# LAMEBOY.net
KiCad netlist of a schematic drawn in EAGLE
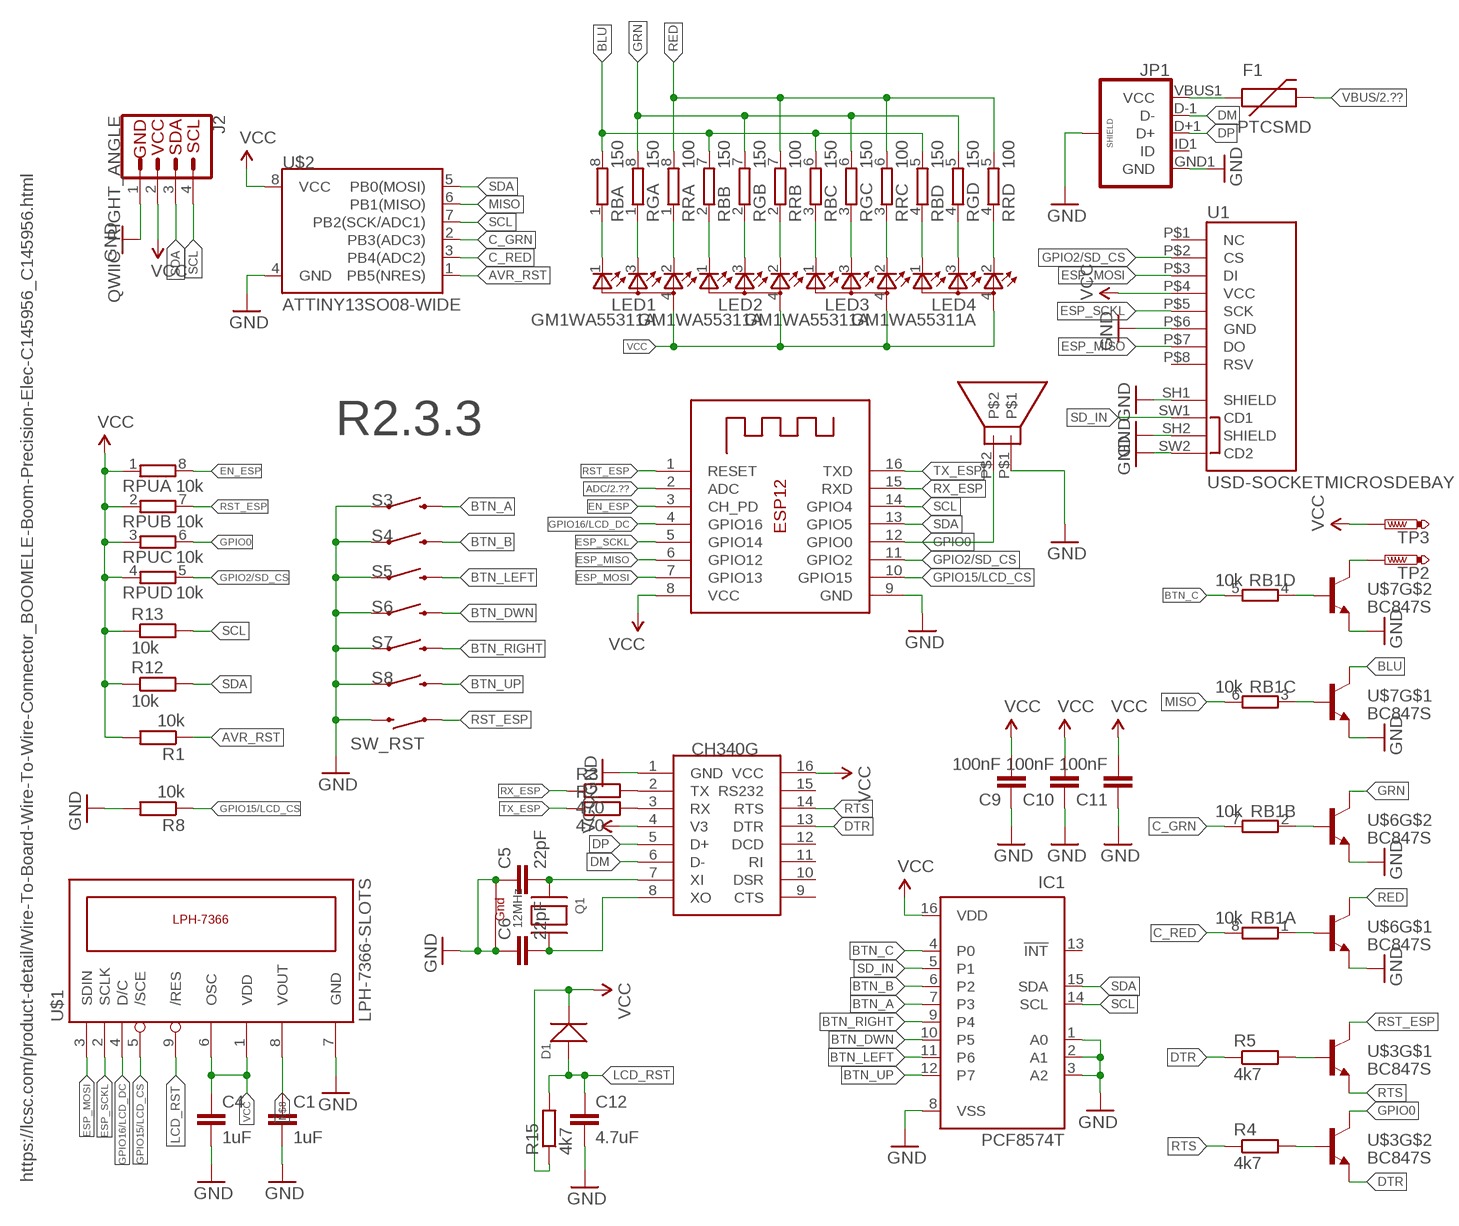
[diagram p0: schematic, sheet 1]
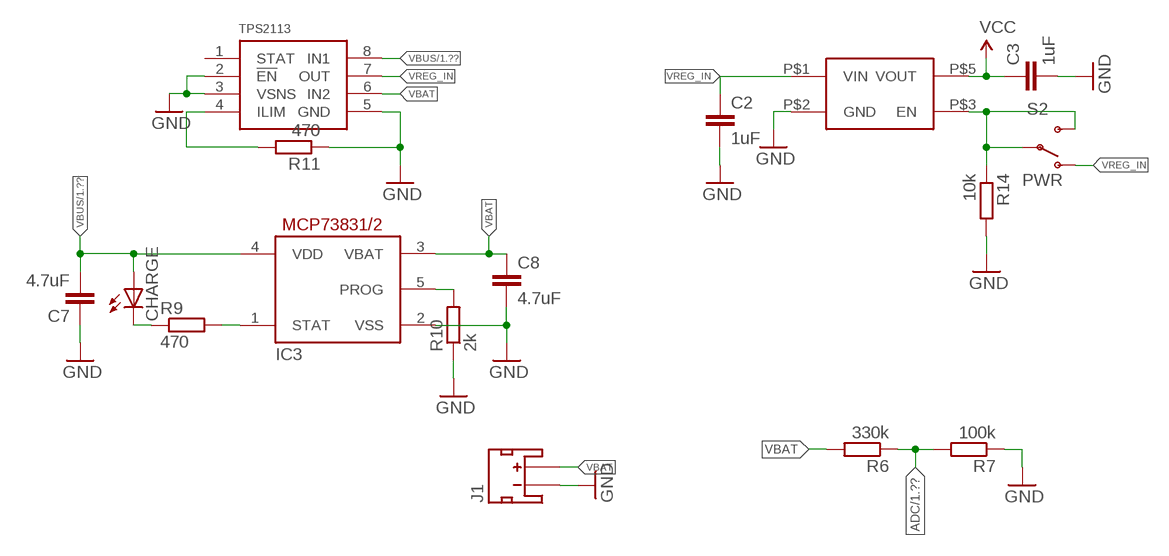
[diagram p1: schematic, sheet 2]

(export (version "E")
  (design (tool "Eeschema 10.0.6"))
  (components
    (comp (ref "C2")
      (value "1uF")
      (footprint "eagle-import:C0805")
      (libsource (lib "eagle-import") (part "C-EUC0805"))
    )
    (comp (ref "C3")
      (value "1uF")
      (footprint "eagle-import:C0805")
      (libsource (lib "eagle-import") (part "C-EUC0805"))
    )
    (comp (ref "C7")
      (value "4.7uF")
      (footprint "eagle-import:C0805")
      (libsource (lib "eagle-import") (part "C-EUC0805"))
    )
    (comp (ref "C8")
      (value "4.7uF")
      (footprint "eagle-import:C0805")
      (libsource (lib "eagle-import") (part "C-EUC0805"))
    )
    (comp (ref "CHARGE")
      (value "LEDCHARLIE")
      (footprint "eagle-import:CHIPLED_0603_CHARLIE")
      (libsource (lib "eagle-import") (part "LEDCHARLIE"))
    )
    (comp (ref "IC3")
      (value "MCP73831")
      (footprint "eagle-import:SOT23-5L")
      (libsource (lib "eagle-import") (part "MCP73831/OT"))
    )
    (comp (ref "J1")
      (value "JST_2MM_MALE")
      (footprint "eagle-import:JST-2-SMD")
      (libsource (lib "eagle-import") (part "JST_2MM_MALE"))
    )
    (comp (ref "R6")
      (value "330k")
      (footprint "eagle-import:R0603")
      (libsource (lib "eagle-import") (part "R-EU_R0603"))
    )
    (comp (ref "R7")
      (value "100k")
      (footprint "eagle-import:R0603")
      (libsource (lib "eagle-import") (part "R-EU_R0603"))
    )
    (comp (ref "R9")
      (value "470")
      (footprint "eagle-import:R0603")
      (libsource (lib "eagle-import") (part "R-EU_R0603"))
    )
    (comp (ref "R10")
      (value "2k")
      (footprint "eagle-import:R0603")
      (libsource (lib "eagle-import") (part "R-EU_R0603"))
    )
    (comp (ref "R11")
      (value "470")
      (footprint "eagle-import:R0603")
      (libsource (lib "eagle-import") (part "R-EU_R0603"))
    )
    (comp (ref "R14")
      (value "10k")
      (footprint "eagle-import:R0603")
      (libsource (lib "eagle-import") (part "R-EU_R0603"))
    )
    (comp (ref "S2")
      (value "PWR")
      (footprint "eagle-import:SWITCH-SPST-SMD-A")
      (libsource (lib "eagle-import") (part "SWITCH-SPDT-SMD-A"))
    )
    (comp (ref "U$4")
      (value "TPS2113-PW")
      (footprint "eagle-import:TEXAS-PW")
      (libsource (lib "eagle-import") (part "TPS2113-PW"))
    )
    (comp (ref "U$9")
      (value "AP2112KAP2112K")
      (footprint "eagle-import:AP2112")
      (libsource (lib "eagle-import") (part "AP2112KAP2112K"))
    )
    (comp (ref "C1")
      (value "1uF")
      (footprint "eagle-import:C0805")
      (libsource (lib "eagle-import") (part "C-EUC0805"))
    )
    (comp (ref "C4")
      (value "1uF")
      (footprint "eagle-import:C0805")
      (libsource (lib "eagle-import") (part "C-EUC0805"))
    )
    (comp (ref "C5")
      (value "22pF")
      (footprint "eagle-import:C0805")
      (libsource (lib "eagle-import") (part "C-EUC0805"))
    )
    (comp (ref "C6")
      (value "22pF")
      (footprint "eagle-import:C0805")
      (libsource (lib "eagle-import") (part "C-EUC0805"))
    )
    (comp (ref "C9")
      (value "100nF")
      (footprint "eagle-import:C0805")
      (libsource (lib "eagle-import") (part "C-EUC0805"))
    )
    (comp (ref "C10")
      (value "100nF")
      (footprint "eagle-import:C0805")
      (libsource (lib "eagle-import") (part "C-EUC0805"))
    )
    (comp (ref "C11")
      (value "100nF")
      (footprint "eagle-import:C0805")
      (libsource (lib "eagle-import") (part "C-EUC0805"))
    )
    (comp (ref "C12")
      (value "4.7uF")
      (footprint "eagle-import:C0805")
      (libsource (lib "eagle-import") (part "C-EUC0805"))
    )
    (comp (ref "CH340G")
      (value "CH340GCH340G")
      (footprint "eagle-import:SOIC16")
      (libsource (lib "eagle-import") (part "CH340GCH340G"))
    )
    (comp (ref "D1")
      (value "DIODE'1N4148-SMD'")
      (footprint "eagle-import:LL-34")
      (libsource (lib "eagle-import") (part "DIODE'1N4148-SMD'"))
    )
    (comp (ref "F1")
      (value "PTCSMD")
      (footprint "eagle-import:PTC-1206")
      (libsource (lib "eagle-import") (part "PTCSMD"))
    )
    (comp (ref "IC1")
      (value "PCF8574T")
      (footprint "eagle-import:SO16W")
      (fields (field (name "MPN") "PCF8574T/3,512"))
      (libsource (lib "eagle-import") (part "PCF8574T"))
    )
    (comp (ref "J2")
      (value "QWIIC_RIGHT_ANGLE")
      (footprint "eagle-import:JST04_1MM_RA")
      (libsource (lib "eagle-import") (part "QWIIC_CONNECTORJS-1MM"))
    )
    (comp (ref "JP1")
      (value "USB_MICROB_PLUG-IDK")
      (footprint "eagle-import:USB-AB-MICRO-SMD_SLOT")
      (libsource (lib "eagle-import") (part "USB_MICROB_PLUG-IDK"))
    )
    (comp (ref "LED1")
      (value "GM1WA55311A")
      (footprint "eagle-import:GM1WA55311A")
      (libsource (lib "eagle-import") (part "GM1WA55311A"))
    )
    (comp (ref "LED2")
      (value "GM1WA55311A")
      (footprint "eagle-import:GM1WA55311A")
      (libsource (lib "eagle-import") (part "GM1WA55311A"))
    )
    (comp (ref "LED3")
      (value "GM1WA55311A")
      (footprint "eagle-import:GM1WA55311A")
      (libsource (lib "eagle-import") (part "GM1WA55311A"))
    )
    (comp (ref "LED4")
      (value "GM1WA55311A")
      (footprint "eagle-import:GM1WA55311A")
      (libsource (lib "eagle-import") (part "GM1WA55311A"))
    )
    (comp (ref "Q1")
      (value "12MHz")
      (footprint "eagle-import:NX3225_BIGGER")
      (libsource (lib "eagle-import") (part "XTAL-4BIGGER"))
    )
    (comp (ref "R1")
      (value "10k")
      (footprint "eagle-import:R0603")
      (libsource (lib "eagle-import") (part "R-EU_R0603"))
    )
    (comp (ref "R2")
      (value "470")
      (footprint "eagle-import:R0603")
      (libsource (lib "eagle-import") (part "R-EU_R0603"))
    )
    (comp (ref "R3")
      (value "470")
      (footprint "eagle-import:R0603")
      (libsource (lib "eagle-import") (part "R-EU_R0603"))
    )
    (comp (ref "R4")
      (value "4k7")
      (footprint "eagle-import:R0603")
      (libsource (lib "eagle-import") (part "R-EU_R0603"))
    )
    (comp (ref "R5")
      (value "4k7")
      (footprint "eagle-import:R0603")
      (libsource (lib "eagle-import") (part "R-EU_R0603"))
    )
    (comp (ref "R8")
      (value "10k")
      (footprint "eagle-import:R0603")
      (libsource (lib "eagle-import") (part "R-EU_R0603"))
    )
    (comp (ref "R12")
      (value "10k")
      (footprint "eagle-import:R0603")
      (libsource (lib "eagle-import") (part "R-EU_R0603"))
    )
    (comp (ref "R13")
      (value "10k")
      (footprint "eagle-import:R0603")
      (libsource (lib "eagle-import") (part "R-EU_R0603"))
    )
    (comp (ref "R15")
      (value "4k7")
      (footprint "eagle-import:R0603")
      (libsource (lib "eagle-import") (part "R-EU_R0603"))
    )
    (comp (ref "RB")
      (value "150")
      (footprint "eagle-import:0603-ARC")
      (libsource (lib "eagle-import") (part "4R-N0603-ARC"))
    )
    (comp (ref "RB1")
      (value "10k")
      (footprint "eagle-import:0603-ARC")
      (libsource (lib "eagle-import") (part "4R-N0603-ARC"))
    )
    (comp (ref "RG")
      (value "150")
      (footprint "eagle-import:0603-ARC")
      (libsource (lib "eagle-import") (part "4R-N0603-ARC"))
    )
    (comp (ref "RPU")
      (value "10k")
      (footprint "eagle-import:0603-ARC")
      (libsource (lib "eagle-import") (part "4R-N0603-ARC"))
    )
    (comp (ref "RR")
      (value "100")
      (footprint "eagle-import:0603-ARC")
      (libsource (lib "eagle-import") (part "4R-N0603-ARC"))
    )
    (comp (ref "S3")
      (value "SWITCH-MOMENTARY-2SMD-4")
      (footprint "eagle-import:TACTILE_SWITCH_TALL")
      (libsource (lib "eagle-import") (part "SWITCH-MOMENTARY-2SMD-4"))
    )
    (comp (ref "S4")
      (value "SWITCH-MOMENTARY-2SMD-4")
      (footprint "eagle-import:TACTILE_SWITCH_TALL")
      (libsource (lib "eagle-import") (part "SWITCH-MOMENTARY-2SMD-4"))
    )
    (comp (ref "S5")
      (value "SWITCH-MOMENTARY-2SMD-4")
      (footprint "eagle-import:TACTILE_SWITCH_TALL")
      (libsource (lib "eagle-import") (part "SWITCH-MOMENTARY-2SMD-4"))
    )
    (comp (ref "S6")
      (value "SWITCH-MOMENTARY-2SMD-4")
      (footprint "eagle-import:TACTILE_SWITCH_TALL")
      (libsource (lib "eagle-import") (part "SWITCH-MOMENTARY-2SMD-4"))
    )
    (comp (ref "S7")
      (value "SWITCH-MOMENTARY-2SMD-4")
      (footprint "eagle-import:TACTILE_SWITCH_TALL")
      (libsource (lib "eagle-import") (part "SWITCH-MOMENTARY-2SMD-4"))
    )
    (comp (ref "S8")
      (value "SWITCH-MOMENTARY-2SMD-4")
      (footprint "eagle-import:TACTILE_SWITCH_TALL")
      (libsource (lib "eagle-import") (part "SWITCH-MOMENTARY-2SMD-4"))
    )
    (comp (ref "SW_RST")
      (value "SWITCH-MOMENTARY-2-SMD-1101NE")
      (footprint "eagle-import:TACTILE-SWITCH-1101NE")
      (libsource (lib "eagle-import") (part "SWITCH-MOMENTARY-2-SMD-1101NE"))
    )
    (comp (ref "TP2")
      (value "PTR1B1,27")
      (footprint "eagle-import:B1,27")
      (libsource (lib "eagle-import") (part "PTR1B1,27"))
    )
    (comp (ref "TP3")
      (value "PTR1B1,27")
      (footprint "eagle-import:B1,27")
      (libsource (lib "eagle-import") (part "PTR1B1,27"))
    )
    (comp (ref "U$1")
      (value "LPH-7366-SLOTS")
      (footprint "eagle-import:LPH-7366-SLOTS")
      (libsource (lib "eagle-import") (part "LPH-7366-SLOTS"))
    )
    (comp (ref "U$2")
      (value "ATTINY13SO08-WIDE")
      (footprint "eagle-import:SO08-EIAJ")
      (libsource (lib "eagle-import") (part "ATTINY13SO08-WIDE"))
    )
    (comp (ref "U$3")
      (value "BC847S")
      (footprint "eagle-import:SOT363")
      (libsource (lib "eagle-import") (part "MMDT3904"))
    )
    (comp (ref "U$5")
      (value "SPEAKERKMTG-1102")
      (footprint "eagle-import:KMTG-1102")
      (libsource (lib "eagle-import") (part "SPEAKERKMTG-1102"))
    )
    (comp (ref "U$6")
      (value "BC847S")
      (footprint "eagle-import:SOT363")
      (libsource (lib "eagle-import") (part "MMDT3904"))
    )
    (comp (ref "U$7")
      (value "BC847S")
      (footprint "eagle-import:SOT363")
      (libsource (lib "eagle-import") (part "MMDT3904"))
    )
    (comp (ref "U1")
      (value "USD-SOCKETMICROSDEBAY")
      (footprint "eagle-import:MICRO-SD-SOCKET-EBAY")
      (libsource (lib "eagle-import") (part "USD-SOCKETMICROSDEBAY"))
    )
    (comp (ref "X1")
      (value "ESP-12")
      (footprint "eagle-import:ESP-12")
      (libsource (lib "eagle-import") (part "ESP-12"))
    )
  )
  (nets
    (net (code "1") (name "ADC") (class "Default")
      (node (ref "R6") (pin "1") (pinfunction "1_1") (pintype "passive"))
      (node (ref "R7") (pin "2") (pinfunction "2_2") (pintype "passive"))
      (node (ref "X1") (pin "2") (pinfunction "ADC_2") (pintype "passive"))
    )
    (net (code "2") (name "AVR_RST") (class "Default")
      (node (ref "R1") (pin "1") (pinfunction "1_1") (pintype "passive"))
      (node (ref "U$2") (pin "1") (pinfunction "PB5(NRES)_1") (pintype "bidirectional"))
    )
    (net (code "3") (name "BLU") (class "Default")
      (node (ref "RB") (pin "5") (pinfunction "2_5") (pintype "passive"))
      (node (ref "RB") (pin "6") (pinfunction "2_6") (pintype "passive"))
      (node (ref "RB") (pin "7") (pinfunction "2_7") (pintype "passive"))
      (node (ref "RB") (pin "8") (pinfunction "2_8") (pintype "passive"))
      (node (ref "U$7") (pin "3") (pinfunction "C_3") (pintype "passive"))
    )
    (net (code "4") (name "BTN_A") (class "Default")
      (node (ref "IC1") (pin "7") (pinfunction "P3_7") (pintype "bidirectional"))
      (node (ref "S3") (pin "B2") (pinfunction "2_B2") (pintype "passive"))
    )
    (net (code "5") (name "BTN_B") (class "Default")
      (node (ref "IC1") (pin "6") (pinfunction "P2_6") (pintype "bidirectional"))
      (node (ref "S4") (pin "B2") (pinfunction "2_B2") (pintype "passive"))
    )
    (net (code "6") (name "BTN_C") (class "Default")
      (node (ref "IC1") (pin "4") (pinfunction "P0_4") (pintype "bidirectional"))
      (node (ref "RB1") (pin "5") (pinfunction "2_5") (pintype "passive"))
    )
    (net (code "7") (name "BTN_DWN") (class "Default")
      (node (ref "IC1") (pin "10") (pinfunction "P5_10") (pintype "bidirectional"))
      (node (ref "S6") (pin "B2") (pinfunction "2_B2") (pintype "passive"))
    )
    (net (code "8") (name "BTN_LEFT") (class "Default")
      (node (ref "IC1") (pin "11") (pinfunction "P6_11") (pintype "bidirectional"))
      (node (ref "S5") (pin "B2") (pinfunction "2_B2") (pintype "passive"))
    )
    (net (code "9") (name "BTN_RIGHT") (class "Default")
      (node (ref "IC1") (pin "9") (pinfunction "P4_9") (pintype "bidirectional"))
      (node (ref "S7") (pin "B2") (pinfunction "2_B2") (pintype "passive"))
    )
    (net (code "10") (name "BTN_UP") (class "Default")
      (node (ref "IC1") (pin "12") (pinfunction "P7_12") (pintype "bidirectional"))
      (node (ref "S8") (pin "B2") (pinfunction "2_B2") (pintype "passive"))
    )
    (net (code "11") (name "C_GRN") (class "Default")
      (node (ref "RB1") (pin "7") (pinfunction "2_7") (pintype "passive"))
      (node (ref "U$2") (pin "2") (pinfunction "PB3(ADC3)_2") (pintype "bidirectional"))
    )
    (net (code "12") (name "C_RED") (class "Default")
      (node (ref "RB1") (pin "8") (pinfunction "2_8") (pintype "passive"))
      (node (ref "U$2") (pin "3") (pinfunction "PB4(ADC2)_3") (pintype "bidirectional"))
    )
    (net (code "13") (name "DM") (class "Default")
      (node (ref "CH340G") (pin "6") (pinfunction "D-_6") (pintype "bidirectional"))
      (node (ref "JP1") (pin "D-1") (pinfunction "D-_D-1") (pintype "bidirectional"))
    )
    (net (code "14") (name "DP") (class "Default")
      (node (ref "CH340G") (pin "5") (pinfunction "D+_5") (pintype "bidirectional"))
      (node (ref "JP1") (pin "D+1") (pinfunction "D+_D+1") (pintype "bidirectional"))
    )
    (net (code "15") (name "DTR") (class "Default")
      (node (ref "CH340G") (pin "13") (pinfunction "DTR_13") (pintype "bidirectional"))
      (node (ref "R5") (pin "1") (pinfunction "1_1") (pintype "passive"))
      (node (ref "U$3") (pin "1") (pinfunction "E_1") (pintype "passive"))
    )
    (net (code "16") (name "EN_ESP") (class "Default")
      (node (ref "RPU") (pin "8") (pinfunction "2_8") (pintype "passive"))
      (node (ref "X1") (pin "3") (pinfunction "CH_PD_3") (pintype "input"))
    )
    (net (code "17") (name "ESP_MISO") (class "Default")
      (node (ref "U1") (pin "P$7") (pinfunction "DO_P$7") (pintype "bidirectional"))
      (node (ref "X1") (pin "6") (pinfunction "GPIO12_6") (pintype "bidirectional"))
    )
    (net (code "18") (name "ESP_MOSI") (class "Default")
      (node (ref "U$1") (pin "3") (pinfunction "SDIN_3") (pintype "input"))
      (node (ref "U1") (pin "P$3") (pinfunction "DI_P$3") (pintype "bidirectional"))
      (node (ref "X1") (pin "7") (pinfunction "GPIO13_7") (pintype "bidirectional"))
    )
    (net (code "19") (name "ESP_SCKL") (class "Default")
      (node (ref "U$1") (pin "2") (pinfunction "SCLK_2") (pintype "input"))
      (node (ref "U1") (pin "P$5") (pinfunction "SCK_P$5") (pintype "bidirectional"))
      (node (ref "X1") (pin "5") (pinfunction "GPIO14_5") (pintype "bidirectional"))
    )
    (net (code "20") (name "GND") (class "Default")
      (node (ref "C1") (pin "2") (pinfunction "2_2") (pintype "passive"))
      (node (ref "C10") (pin "1") (pinfunction "1_1") (pintype "passive"))
      (node (ref "C11") (pin "1") (pinfunction "1_1") (pintype "passive"))
      (node (ref "C12") (pin "2") (pinfunction "2_2") (pintype "passive"))
      (node (ref "C2") (pin "2") (pinfunction "2_2") (pintype "passive"))
      (node (ref "C3") (pin "2") (pinfunction "2_2") (pintype "passive"))
      (node (ref "C4") (pin "2") (pinfunction "2_2") (pintype "passive"))
      (node (ref "C5") (pin "1") (pinfunction "1_1") (pintype "passive"))
      (node (ref "C6") (pin "1") (pinfunction "1_1") (pintype "passive"))
      (node (ref "C7") (pin "1") (pinfunction "1_1") (pintype "passive"))
      (node (ref "C8") (pin "2") (pinfunction "2_2") (pintype "passive"))
      (node (ref "C9") (pin "1") (pinfunction "1_1") (pintype "passive"))
      (node (ref "CH340G") (pin "1") (pinfunction "GND_1") (pintype "bidirectional"))
      (node (ref "IC1") (pin "1") (pinfunction "A0_1") (pintype "input"))
      (node (ref "IC1") (pin "2") (pinfunction "A1_2") (pintype "input"))
      (node (ref "IC1") (pin "3") (pinfunction "A2_3") (pintype "input"))
      (node (ref "IC1") (pin "8") (pinfunction "VSS_8") (pintype "power_in"))
      (node (ref "IC3") (pin "2") (pinfunction "VSS_2") (pintype "power_in"))
      (node (ref "J1") (pin "1") (pinfunction "-_1") (pintype "bidirectional"))
      (node (ref "J2") (pin "1") (pinfunction "1_1") (pintype "power_in"))
      (node (ref "JP1") (pin "GND1") (pinfunction "GND_GND1") (pintype "bidirectional"))
      (node (ref "JP1") (pin "P$1") (pinfunction "SHIELD_P$1") (pintype "bidirectional"))
      (node (ref "JP1") (pin "P$2") (pinfunction "SHIELD_P$2") (pintype "bidirectional"))
      (node (ref "JP1") (pin "P$3") (pinfunction "SHIELD_P$3") (pintype "bidirectional"))
      (node (ref "JP1") (pin "P$4") (pinfunction "SHIELD_P$4") (pintype "bidirectional"))
      (node (ref "Q1") (pin "2") (pinfunction "G2_2") (pintype "power_in"))
      (node (ref "Q1") (pin "4") (pinfunction "G1_4") (pintype "power_in"))
      (node (ref "R10") (pin "1") (pinfunction "1_1") (pintype "passive"))
      (node (ref "R11") (pin "1") (pinfunction "1_1") (pintype "passive"))
      (node (ref "R14") (pin "2") (pinfunction "2_2") (pintype "passive"))
      (node (ref "R7") (pin "1") (pinfunction "1_1") (pintype "passive"))
      (node (ref "R8") (pin "2") (pinfunction "2_2") (pintype "passive"))
      (node (ref "S3") (pin "A2") (pinfunction "1_A2") (pintype "passive"))
      (node (ref "S4") (pin "A2") (pinfunction "1_A2") (pintype "passive"))
      (node (ref "S5") (pin "A2") (pinfunction "1_A2") (pintype "passive"))
      (node (ref "S6") (pin "A2") (pinfunction "1_A2") (pintype "passive"))
      (node (ref "S7") (pin "A2") (pinfunction "1_A2") (pintype "passive"))
      (node (ref "S8") (pin "A2") (pinfunction "1_A2") (pintype "passive"))
      (node (ref "SW_RST") (pin "P$2") (pinfunction "2_P$2") (pintype "passive"))
      (node (ref "U$1") (pin "7") (pinfunction "GND_7") (pintype "power_in"))
      (node (ref "U$2") (pin "4") (pinfunction "GND_4") (pintype "bidirectional"))
      (node (ref "U$4") (pin "2") (pinfunction "~{EN}_2") (pintype "bidirectional"))
      (node (ref "U$4") (pin "3") (pinfunction "VSNS_3") (pintype "bidirectional"))
      (node (ref "U$4") (pin "5") (pinfunction "GND_5") (pintype "bidirectional"))
      (node (ref "U$5") (pin "P$1") (pinfunction "P$1_P$1") (pintype "bidirectional"))
      (node (ref "U$6") (pin "1") (pinfunction "E_1") (pintype "passive"))
      (node (ref "U$6") (pin "4") (pinfunction "E_4") (pintype "passive"))
      (node (ref "U$7") (pin "1") (pinfunction "E_1") (pintype "passive"))
      (node (ref "U$7") (pin "4") (pinfunction "E_4") (pintype "passive"))
      (node (ref "U$9") (pin "P$2") (pinfunction "GND_P$2") (pintype "bidirectional"))
      (node (ref "U1") (pin "P$6") (pinfunction "GND_P$6") (pintype "bidirectional"))
      (node (ref "U1") (pin "SH1") (pinfunction "SHIELD_SH1") (pintype "bidirectional"))
      (node (ref "U1") (pin "SH2") (pinfunction "SHIELD_SH2") (pintype "bidirectional"))
      (node (ref "U1") (pin "SW2") (pinfunction "CD2_SW2") (pintype "bidirectional"))
      (node (ref "X1") (pin "9") (pinfunction "GND_9") (pintype "power_in"))
    )
    (net (code "21") (name "GPIO0") (class "Default")
      (node (ref "RPU") (pin "6") (pinfunction "2_6") (pintype "passive"))
      (node (ref "U$3") (pin "6") (pinfunction "C_6") (pintype "passive"))
      (node (ref "U$5") (pin "P$2") (pinfunction "P$2_P$2") (pintype "bidirectional"))
      (node (ref "X1") (pin "12") (pinfunction "GPIO0_12") (pintype "bidirectional"))
    )
    (net (code "22") (name "GPIO2{slash}SD_CS") (class "Default")
      (node (ref "RPU") (pin "5") (pinfunction "2_5") (pintype "passive"))
      (node (ref "U1") (pin "P$2") (pinfunction "CS_P$2") (pintype "bidirectional"))
      (node (ref "X1") (pin "11") (pinfunction "GPIO2_11") (pintype "bidirectional"))
    )
    (net (code "23") (name "GPIO15{slash}LCD_CS") (class "Default")
      (node (ref "R8") (pin "1") (pinfunction "1_1") (pintype "passive"))
      (node (ref "U$1") (pin "5") (pinfunction "/SCE_5") (pintype "input"))
      (node (ref "X1") (pin "10") (pinfunction "GPIO15_10") (pintype "bidirectional"))
    )
    (net (code "24") (name "GPIO16{slash}LCD_DC") (class "Default")
      (node (ref "U$1") (pin "4") (pinfunction "D/C_4") (pintype "input"))
      (node (ref "X1") (pin "4") (pinfunction "GPIO16_4") (pintype "bidirectional"))
    )
    (net (code "25") (name "GRN") (class "Default")
      (node (ref "RG") (pin "5") (pinfunction "2_5") (pintype "passive"))
      (node (ref "RG") (pin "6") (pinfunction "2_6") (pintype "passive"))
      (node (ref "RG") (pin "7") (pinfunction "2_7") (pintype "passive"))
      (node (ref "RG") (pin "8") (pinfunction "2_8") (pintype "passive"))
      (node (ref "U$6") (pin "6") (pinfunction "C_6") (pintype "passive"))
    )
    (net (code "26") (name "LCD_RST") (class "Default")
      (node (ref "C12") (pin "1") (pinfunction "1_1") (pintype "passive"))
      (node (ref "D1") (pin "A") (pinfunction "+_A") (pintype "passive"))
      (node (ref "R15") (pin "2") (pinfunction "2_2") (pintype "passive"))
      (node (ref "U$1") (pin "9") (pinfunction "/RES_9") (pintype "input"))
    )
    (net (code "27") (name "MISO") (class "Default")
      (node (ref "RB1") (pin "6") (pinfunction "2_6") (pintype "passive"))
      (node (ref "U$2") (pin "6") (pinfunction "PB1(MISO)_6") (pintype "bidirectional"))
    )
    (net (code "28") (name "N$8") (class "Default")
      (node (ref "C1") (pin "1") (pinfunction "1_1") (pintype "passive"))
      (node (ref "U$1") (pin "8") (pinfunction "VOUT_8") (pintype "passive"))
    )
    (net (code "29") (name "Net-(CH340G-RX)") (class "Default")
      (node (ref "CH340G") (pin "3") (pinfunction "RX_3") (pintype "bidirectional"))
      (node (ref "R2") (pin "2") (pinfunction "2_2") (pintype "passive"))
    )
    (net (code "30") (name "Net-(CH340G-TX)") (class "Default")
      (node (ref "CH340G") (pin "2") (pinfunction "TX_2") (pintype "bidirectional"))
      (node (ref "R3") (pin "2") (pinfunction "2_2") (pintype "passive"))
    )
    (net (code "31") (name "Net-(CH340G-XI)") (class "Default")
      (node (ref "C5") (pin "2") (pinfunction "2_2") (pintype "passive"))
      (node (ref "CH340G") (pin "7") (pinfunction "XI_7") (pintype "bidirectional"))
      (node (ref "Q1") (pin "1") (pinfunction "X1_1") (pintype "bidirectional"))
    )
    (net (code "32") (name "Net-(CH340G-XO)") (class "Default")
      (node (ref "C6") (pin "2") (pinfunction "2_2") (pintype "passive"))
      (node (ref "CH340G") (pin "8") (pinfunction "XO_8") (pintype "bidirectional"))
      (node (ref "Q1") (pin "3") (pinfunction "X2_3") (pintype "bidirectional"))
    )
    (net (code "33") (name "Net-(CHARGE-PadC)") (class "Default")
      (node (ref "CHARGE") (pin "C") (pinfunction "C_C") (pintype "passive"))
      (node (ref "R9") (pin "1") (pinfunction "1_1") (pintype "passive"))
    )
    (net (code "34") (name "Net-(IC3-PROG)") (class "Default")
      (node (ref "IC3") (pin "5") (pinfunction "PROG_5") (pintype "input"))
      (node (ref "R10") (pin "2") (pinfunction "2_2") (pintype "passive"))
    )
    (net (code "35") (name "Net-(IC3-STAT)") (class "Default")
      (node (ref "IC3") (pin "1") (pinfunction "STAT_1") (pintype "output"))
      (node (ref "R9") (pin "2") (pinfunction "2_2") (pintype "passive"))
    )
    (net (code "36") (name "Net-(JP1-VCC)") (class "Default")
      (node (ref "F1") (pin "1") (pinfunction "1_1") (pintype "bidirectional"))
      (node (ref "JP1") (pin "VBUS1") (pinfunction "VCC_VBUS1") (pintype "bidirectional"))
    )
    (net (code "37") (name "Net-(LED1-CBLUE)") (class "Default")
      (node (ref "LED1") (pin "3") (pinfunction "CBLUE_3") (pintype "passive"))
      (node (ref "RG") (pin "1") (pinfunction "1_1") (pintype "passive"))
    )
    (net (code "38") (name "Net-(LED1-CGREEN)") (class "Default")
      (node (ref "LED1") (pin "1") (pinfunction "CGREEN_1") (pintype "passive"))
      (node (ref "RB") (pin "1") (pinfunction "1_1") (pintype "passive"))
    )
    (net (code "39") (name "Net-(LED1-CRED)") (class "Default")
      (node (ref "LED1") (pin "2") (pinfunction "CRED_2") (pintype "passive"))
      (node (ref "RR") (pin "1") (pinfunction "1_1") (pintype "passive"))
    )
    (net (code "40") (name "Net-(LED2-CBLUE)") (class "Default")
      (node (ref "LED2") (pin "3") (pinfunction "CBLUE_3") (pintype "passive"))
      (node (ref "RG") (pin "2") (pinfunction "1_2") (pintype "passive"))
    )
    (net (code "41") (name "Net-(LED2-CGREEN)") (class "Default")
      (node (ref "LED2") (pin "1") (pinfunction "CGREEN_1") (pintype "passive"))
      (node (ref "RB") (pin "2") (pinfunction "1_2") (pintype "passive"))
    )
    (net (code "42") (name "Net-(LED2-CRED)") (class "Default")
      (node (ref "LED2") (pin "2") (pinfunction "CRED_2") (pintype "passive"))
      (node (ref "RR") (pin "2") (pinfunction "1_2") (pintype "passive"))
    )
    (net (code "43") (name "Net-(LED3-CBLUE)") (class "Default")
      (node (ref "LED3") (pin "3") (pinfunction "CBLUE_3") (pintype "passive"))
      (node (ref "RG") (pin "3") (pinfunction "1_3") (pintype "passive"))
    )
    (net (code "44") (name "Net-(LED3-CGREEN)") (class "Default")
      (node (ref "LED3") (pin "1") (pinfunction "CGREEN_1") (pintype "passive"))
      (node (ref "RB") (pin "3") (pinfunction "1_3") (pintype "passive"))
    )
    (net (code "45") (name "Net-(LED3-CRED)") (class "Default")
      (node (ref "LED3") (pin "2") (pinfunction "CRED_2") (pintype "passive"))
      (node (ref "RR") (pin "3") (pinfunction "1_3") (pintype "passive"))
    )
    (net (code "46") (name "Net-(LED4-CBLUE)") (class "Default")
      (node (ref "LED4") (pin "3") (pinfunction "CBLUE_3") (pintype "passive"))
      (node (ref "RG") (pin "4") (pinfunction "1_4") (pintype "passive"))
    )
    (net (code "47") (name "Net-(LED4-CGREEN)") (class "Default")
      (node (ref "LED4") (pin "1") (pinfunction "CGREEN_1") (pintype "passive"))
      (node (ref "RB") (pin "4") (pinfunction "1_4") (pintype "passive"))
    )
    (net (code "48") (name "Net-(LED4-CRED)") (class "Default")
      (node (ref "LED4") (pin "2") (pinfunction "CRED_2") (pintype "passive"))
      (node (ref "RR") (pin "4") (pinfunction "1_4") (pintype "passive"))
    )
    (net (code "49") (name "Net-(RB1B-1)") (class "Default")
      (node (ref "RB1") (pin "2") (pinfunction "1_2") (pintype "passive"))
      (node (ref "U$6") (pin "2") (pinfunction "B_2") (pintype "passive"))
    )
    (net (code "50") (name "Net-(RB1C-1)") (class "Default")
      (node (ref "RB1") (pin "3") (pinfunction "1_3") (pintype "passive"))
      (node (ref "U$7") (pin "5") (pinfunction "B_5") (pintype "passive"))
    )
    (net (code "51") (name "Net-(RB1D-1)") (class "Default")
      (node (ref "RB1") (pin "4") (pinfunction "1_4") (pintype "passive"))
      (node (ref "U$7") (pin "2") (pinfunction "B_2") (pintype "passive"))
    )
    (net (code "52") (name "Net-(S2-P)") (class "Default")
      (node (ref "R14") (pin "1") (pinfunction "1_1") (pintype "passive"))
      (node (ref "S2") (pin "2") (pinfunction "P_2") (pintype "passive"))
      (node (ref "S2") (pin "3") (pinfunction "S_3") (pintype "passive"))
      (node (ref "U$9") (pin "P$3") (pinfunction "EN_P$3") (pintype "bidirectional"))
    )
    (net (code "53") (name "Net-(U$3A-B)") (class "Default")
      (node (ref "R5") (pin "2") (pinfunction "2_2") (pintype "passive"))
      (node (ref "U$3") (pin "5") (pinfunction "B_5") (pintype "passive"))
    )
    (net (code "54") (name "Net-(U$3B-B)") (class "Default")
      (node (ref "R4") (pin "2") (pinfunction "2_2") (pintype "passive"))
      (node (ref "U$3") (pin "2") (pinfunction "B_2") (pintype "passive"))
    )
    (net (code "55") (name "Net-(U$4-ILIM)") (class "Default")
      (node (ref "R11") (pin "2") (pinfunction "2_2") (pintype "passive"))
      (node (ref "U$4") (pin "4") (pinfunction "ILIM_4") (pintype "bidirectional"))
    )
    (net (code "56") (name "Net-(U$6A-B)") (class "Default")
      (node (ref "RB1") (pin "1") (pinfunction "1_1") (pintype "passive"))
      (node (ref "U$6") (pin "5") (pinfunction "B_5") (pintype "passive"))
    )
    (net (code "57") (name "Net-(U$7B-C)") (class "Default")
      (node (ref "TP2") (pin "TP") (pinfunction "TP_TP") (pintype "input"))
      (node (ref "U$7") (pin "6") (pinfunction "C_6") (pintype "passive"))
    )
    (net (code "58") (name "RED") (class "Default")
      (node (ref "RR") (pin "5") (pinfunction "2_5") (pintype "passive"))
      (node (ref "RR") (pin "6") (pinfunction "2_6") (pintype "passive"))
      (node (ref "RR") (pin "7") (pinfunction "2_7") (pintype "passive"))
      (node (ref "RR") (pin "8") (pinfunction "2_8") (pintype "passive"))
      (node (ref "U$6") (pin "3") (pinfunction "C_3") (pintype "passive"))
    )
    (net (code "59") (name "RST_ESP") (class "Default")
      (node (ref "RPU") (pin "7") (pinfunction "2_7") (pintype "passive"))
      (node (ref "SW_RST") (pin "P$1") (pinfunction "1_P$1") (pintype "passive"))
      (node (ref "U$3") (pin "3") (pinfunction "C_3") (pintype "passive"))
      (node (ref "X1") (pin "1") (pinfunction "RESET_1") (pintype "input"))
    )
    (net (code "60") (name "RTS") (class "Default")
      (node (ref "CH340G") (pin "14") (pinfunction "RTS_14") (pintype "bidirectional"))
      (node (ref "R4") (pin "1") (pinfunction "1_1") (pintype "passive"))
      (node (ref "U$3") (pin "4") (pinfunction "E_4") (pintype "passive"))
    )
    (net (code "61") (name "RX_ESP") (class "Default")
      (node (ref "R3") (pin "1") (pinfunction "1_1") (pintype "passive"))
      (node (ref "X1") (pin "15") (pinfunction "RXD_15") (pintype "input"))
    )
    (net (code "62") (name "SCL") (class "Default")
      (node (ref "IC1") (pin "14") (pinfunction "SCL_14") (pintype "input"))
      (node (ref "J2") (pin "4") (pinfunction "4_4") (pintype "passive"))
      (node (ref "R13") (pin "2") (pinfunction "2_2") (pintype "passive"))
      (node (ref "U$2") (pin "7") (pinfunction "PB2(SCK/ADC1)_7") (pintype "bidirectional"))
      (node (ref "X1") (pin "14") (pinfunction "GPIO4_14") (pintype "bidirectional"))
    )
    (net (code "63") (name "SDA") (class "Default")
      (node (ref "IC1") (pin "15") (pinfunction "SDA_15") (pintype "bidirectional"))
      (node (ref "J2") (pin "3") (pinfunction "3_3") (pintype "passive"))
      (node (ref "R12") (pin "2") (pinfunction "2_2") (pintype "passive"))
      (node (ref "U$2") (pin "5") (pinfunction "PB0(MOSI)_5") (pintype "bidirectional"))
      (node (ref "X1") (pin "13") (pinfunction "GPIO5_13") (pintype "bidirectional"))
    )
    (net (code "64") (name "SD_IN") (class "Default")
      (node (ref "IC1") (pin "5") (pinfunction "P1_5") (pintype "bidirectional"))
      (node (ref "U1") (pin "SW1") (pinfunction "CD1_SW1") (pintype "bidirectional"))
    )
    (net (code "65") (name "TX_ESP") (class "Default")
      (node (ref "R2") (pin "1") (pinfunction "1_1") (pintype "passive"))
      (node (ref "X1") (pin "16") (pinfunction "TXD_16") (pintype "output"))
    )
    (net (code "66") (name "VBAT") (class "Default")
      (node (ref "C8") (pin "1") (pinfunction "1_1") (pintype "passive"))
      (node (ref "IC3") (pin "3") (pinfunction "VBAT_3") (pintype "bidirectional"))
      (node (ref "J1") (pin "2") (pinfunction "+_2") (pintype "bidirectional"))
      (node (ref "R6") (pin "2") (pinfunction "2_2") (pintype "passive"))
      (node (ref "U$4") (pin "6") (pinfunction "IN2_6") (pintype "bidirectional"))
    )
    (net (code "67") (name "VBUS") (class "Default")
      (node (ref "C7") (pin "2") (pinfunction "2_2") (pintype "passive"))
      (node (ref "CHARGE") (pin "A") (pinfunction "A_A") (pintype "passive"))
      (node (ref "F1") (pin "2") (pinfunction "2_2") (pintype "bidirectional"))
      (node (ref "IC3") (pin "4") (pinfunction "VDD_4") (pintype "power_in"))
      (node (ref "U$4") (pin "8") (pinfunction "IN1_8") (pintype "bidirectional"))
    )
    (net (code "68") (name "VCC") (class "Default")
      (node (ref "C10") (pin "2") (pinfunction "2_2") (pintype "passive"))
      (node (ref "C11") (pin "2") (pinfunction "2_2") (pintype "passive"))
      (node (ref "C3") (pin "1") (pinfunction "1_1") (pintype "passive"))
      (node (ref "C4") (pin "1") (pinfunction "1_1") (pintype "passive"))
      (node (ref "C9") (pin "2") (pinfunction "2_2") (pintype "passive"))
      (node (ref "CH340G") (pin "16") (pinfunction "VCC_16") (pintype "bidirectional"))
      (node (ref "CH340G") (pin "4") (pinfunction "V3_4") (pintype "bidirectional"))
      (node (ref "D1") (pin "C") (pinfunction "-_C") (pintype "passive"))
      (node (ref "IC1") (pin "16") (pinfunction "VDD_16") (pintype "power_in"))
      (node (ref "J2") (pin "2") (pinfunction "2_2") (pintype "power_in"))
      (node (ref "LED1") (pin "4") (pinfunction "A_4") (pintype "passive"))
      (node (ref "LED2") (pin "4") (pinfunction "A_4") (pintype "passive"))
      (node (ref "LED3") (pin "4") (pinfunction "A_4") (pintype "passive"))
      (node (ref "LED4") (pin "4") (pinfunction "A_4") (pintype "passive"))
      (node (ref "R1") (pin "2") (pinfunction "2_2") (pintype "passive"))
      (node (ref "R12") (pin "1") (pinfunction "1_1") (pintype "passive"))
      (node (ref "R13") (pin "1") (pinfunction "1_1") (pintype "passive"))
      (node (ref "R15") (pin "1") (pinfunction "1_1") (pintype "passive"))
      (node (ref "RPU") (pin "1") (pinfunction "1_1") (pintype "passive"))
      (node (ref "RPU") (pin "2") (pinfunction "1_2") (pintype "passive"))
      (node (ref "RPU") (pin "3") (pinfunction "1_3") (pintype "passive"))
      (node (ref "RPU") (pin "4") (pinfunction "1_4") (pintype "passive"))
      (node (ref "TP3") (pin "TP") (pinfunction "TP_TP") (pintype "input"))
      (node (ref "U$1") (pin "1") (pinfunction "VDD_1") (pintype "power_in"))
      (node (ref "U$1") (pin "6") (pinfunction "OSC_6") (pintype "passive"))
      (node (ref "U$2") (pin "8") (pinfunction "VCC_8") (pintype "bidirectional"))
      (node (ref "U$9") (pin "P$5") (pinfunction "VOUT_P$5") (pintype "bidirectional"))
      (node (ref "U1") (pin "P$4") (pinfunction "VCC_P$4") (pintype "bidirectional"))
      (node (ref "X1") (pin "8") (pinfunction "VCC_8") (pintype "power_in"))
    )
    (net (code "69") (name "VREG_IN") (class "Default")
      (node (ref "C2") (pin "1") (pinfunction "1_1") (pintype "passive"))
      (node (ref "S2") (pin "1") (pinfunction "O_1") (pintype "passive"))
      (node (ref "U$4") (pin "7") (pinfunction "OUT_7") (pintype "bidirectional"))
      (node (ref "U$9") (pin "P$1") (pinfunction "VIN_P$1") (pintype "bidirectional"))
    )
    (net (code "70") (name "unconnected-(CH340G-CTS-Pad9)") (class "Default")
      (node (ref "CH340G") (pin "9") (pinfunction "CTS_9") (pintype "bidirectional"))
    )
    (net (code "71") (name "unconnected-(CH340G-DCD-Pad12)") (class "Default")
      (node (ref "CH340G") (pin "12") (pinfunction "DCD_12") (pintype "bidirectional"))
    )
    (net (code "72") (name "unconnected-(CH340G-DSR-Pad10)") (class "Default")
      (node (ref "CH340G") (pin "10") (pinfunction "DSR_10") (pintype "bidirectional"))
    )
    (net (code "73") (name "unconnected-(CH340G-RI-Pad11)") (class "Default")
      (node (ref "CH340G") (pin "11") (pinfunction "RI_11") (pintype "bidirectional"))
    )
    (net (code "74") (name "unconnected-(CH340G-RS232-Pad15)") (class "Default")
      (node (ref "CH340G") (pin "15") (pinfunction "RS232_15") (pintype "bidirectional"))
    )
    (net (code "75") (name "unconnected-(IC1-~{INT}-Pad13)") (class "Default")
      (node (ref "IC1") (pin "13") (pinfunction "~{INT}_13") (pintype "output"))
    )
    (net (code "76") (name "unconnected-(J1-PAD1-PadNC1)") (class "Default")
      (node (ref "J1") (pin "NC1") (pinfunction "PAD1_NC1") (pintype "bidirectional"))
    )
    (net (code "77") (name "unconnected-(J1-PAD2-PadNC2)") (class "Default")
      (node (ref "J1") (pin "NC2") (pinfunction "PAD2_NC2") (pintype "bidirectional"))
    )
    (net (code "78") (name "unconnected-(JP1-ID-PadID1)") (class "Default")
      (node (ref "JP1") (pin "ID1") (pinfunction "ID_ID1") (pintype "bidirectional"))
    )
    (net (code "79") (name "unconnected-(U$4-STAT-Pad1)") (class "Default")
      (node (ref "U$4") (pin "1") (pinfunction "STAT_1") (pintype "bidirectional"))
    )
    (net (code "80") (name "unconnected-(U1-NC-PadP$1)") (class "Default")
      (node (ref "U1") (pin "P$1") (pinfunction "NC_P$1") (pintype "bidirectional"))
    )
    (net (code "81") (name "unconnected-(U1-RSV-PadP$8)") (class "Default")
      (node (ref "U1") (pin "P$8") (pinfunction "RSV_P$8") (pintype "bidirectional"))
    )
  )
)
